# SW_SMALL.net
KiCad netlist of a schematic drawn in Altium Designer
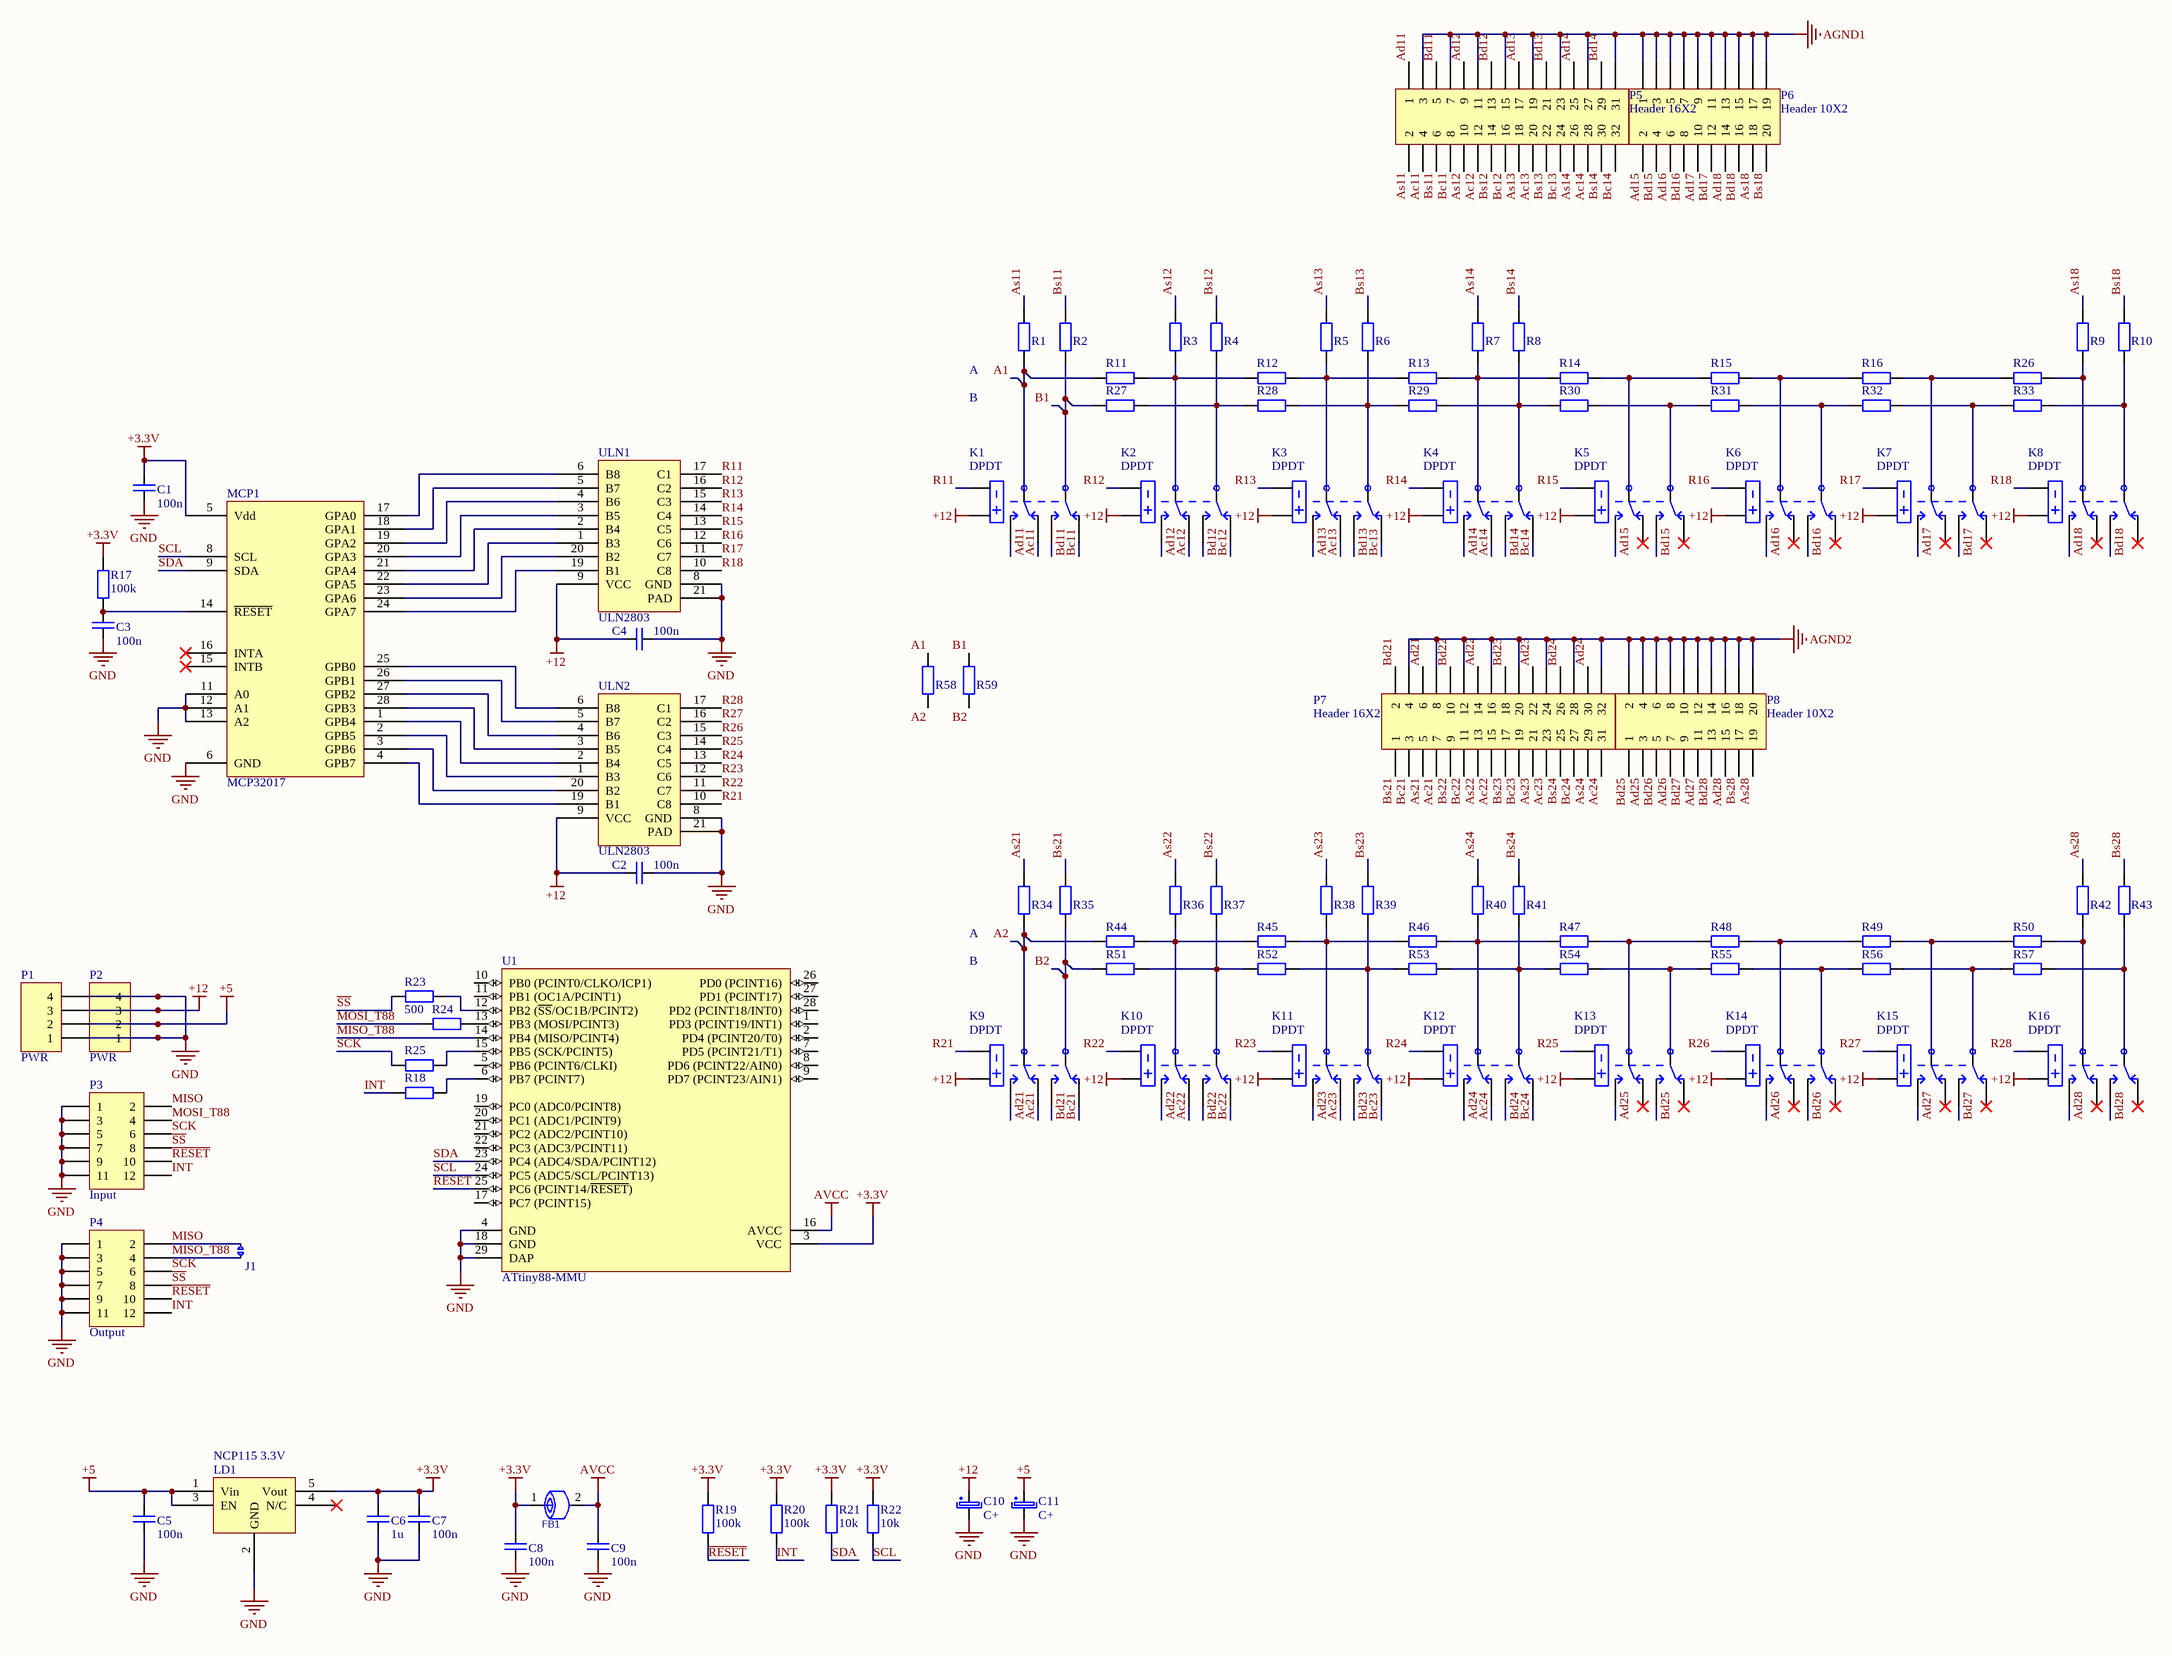
[diagram p0: SW SMALL.SchDoc]

(export (version "E")
  (design (tool "Eeschema 10.0.6"))
  (components
    (comp (ref "C1")
      (value "100n")
      (footprint "R1005_0402i_L")
      (description "Capacitor")
      (libsource (lib "General") (part "C"))
    )
    (comp (ref "C2")
      (value "100n")
      (footprint "R1005_0402i_L")
      (description "Capacitor")
      (libsource (lib "General") (part "C"))
    )
    (comp (ref "C3")
      (value "100n")
      (footprint "R1005_0402i_L")
      (description "Capacitor")
      (libsource (lib "General") (part "C"))
    )
    (comp (ref "C4")
      (value "100n")
      (footprint "R1005_0402i_L")
      (description "Capacitor")
      (libsource (lib "General") (part "C"))
    )
    (comp (ref "C5")
      (value "100n")
      (footprint "R1005_0402i_L")
      (description "Capacitor")
      (libsource (lib "General") (part "C"))
    )
    (comp (ref "C6")
      (value "1u")
      (footprint "C1608_0603I_L")
      (description "Capacitor")
      (libsource (lib "General") (part "C"))
    )
    (comp (ref "C7")
      (value "100n")
      (footprint "R1005_0402i_L")
      (description "Capacitor")
      (libsource (lib "General") (part "C"))
    )
    (comp (ref "C8")
      (value "100n")
      (footprint "R1005_0402i_L")
      (description "Capacitor")
      (libsource (lib "General") (part "C"))
    )
    (comp (ref "C9")
      (value "100n")
      (footprint "R1005_0402i_L")
      (description "Capacitor")
      (libsource (lib "General") (part "C"))
    )
    (comp (ref "C10")
      (value "C+")
      (footprint "C AlElko 5x11 R2")
      (description "Capacitor Polarized")
      (libsource (lib "General") (part "C+"))
    )
    (comp (ref "C11")
      (value "C+")
      (footprint "C AlElko 5x11 R2")
      (description "Capacitor Polarized")
      (libsource (lib "General") (part "C+"))
    )
    (comp (ref "FB1")
      (value "FERITTE BEAD")
      (footprint "R1608_0603I_L")
      (libsource (lib "General") (part "FERITTE BEAD"))
    )
    (comp (ref "J1")
      (value "Terminator")
      (footprint "solderJumper")
      (libsource (lib "Kon_Tipk") (part "JMP_mini"))
    )
    (comp (ref "K1")
      (value "DPDT")
      (footprint "AXICOM IM-G Relay")
      (description "TE CONNECTIVITY  IM-GR  RELAY, DPDT, NO")
      (libsource (lib "DistopikAltiumLibrary") (part "IM-GR Relay DPDT"))
    )
    (comp (ref "K2")
      (value "DPDT")
      (footprint "AXICOM IM-G Relay")
      (description "TE CONNECTIVITY  IM-GR  RELAY, DPDT, NO")
      (libsource (lib "DistopikAltiumLibrary") (part "IM-GR Relay DPDT"))
    )
    (comp (ref "K3")
      (value "DPDT")
      (footprint "AXICOM IM-G Relay")
      (description "TE CONNECTIVITY  IM-GR  RELAY, DPDT, NO")
      (libsource (lib "DistopikAltiumLibrary") (part "IM-GR Relay DPDT"))
    )
    (comp (ref "K4")
      (value "DPDT")
      (footprint "AXICOM IM-G Relay")
      (description "TE CONNECTIVITY  IM-GR  RELAY, DPDT, NO")
      (libsource (lib "DistopikAltiumLibrary") (part "IM-GR Relay DPDT"))
    )
    (comp (ref "K5")
      (value "DPDT")
      (footprint "AXICOM IM-G Relay")
      (description "TE CONNECTIVITY  IM-GR  RELAY, DPDT, NO")
      (libsource (lib "DistopikAltiumLibrary") (part "IM-GR Relay DPDT"))
    )
    (comp (ref "K6")
      (value "DPDT")
      (footprint "AXICOM IM-G Relay")
      (description "TE CONNECTIVITY  IM-GR  RELAY, DPDT, NO")
      (libsource (lib "DistopikAltiumLibrary") (part "IM-GR Relay DPDT"))
    )
    (comp (ref "K7")
      (value "DPDT")
      (footprint "AXICOM IM-G Relay")
      (description "TE CONNECTIVITY  IM-GR  RELAY, DPDT, NO")
      (libsource (lib "DistopikAltiumLibrary") (part "IM-GR Relay DPDT"))
    )
    (comp (ref "K8")
      (value "DPDT")
      (footprint "AXICOM IM-G Relay")
      (description "TE CONNECTIVITY  IM-GR  RELAY, DPDT, NO")
      (libsource (lib "DistopikAltiumLibrary") (part "IM-GR Relay DPDT"))
    )
    (comp (ref "K9")
      (value "DPDT")
      (footprint "AXICOM IM-G Relay")
      (description "TE CONNECTIVITY  IM-GR  RELAY, DPDT, NO")
      (libsource (lib "DistopikAltiumLibrary") (part "IM-GR Relay DPDT"))
    )
    (comp (ref "K10")
      (value "DPDT")
      (footprint "AXICOM IM-G Relay")
      (description "TE CONNECTIVITY  IM-GR  RELAY, DPDT, NO")
      (libsource (lib "DistopikAltiumLibrary") (part "IM-GR Relay DPDT"))
    )
    (comp (ref "K11")
      (value "DPDT")
      (footprint "AXICOM IM-G Relay")
      (description "TE CONNECTIVITY  IM-GR  RELAY, DPDT, NO")
      (libsource (lib "DistopikAltiumLibrary") (part "IM-GR Relay DPDT"))
    )
    (comp (ref "K12")
      (value "DPDT")
      (footprint "AXICOM IM-G Relay")
      (description "TE CONNECTIVITY  IM-GR  RELAY, DPDT, NO")
      (libsource (lib "DistopikAltiumLibrary") (part "IM-GR Relay DPDT"))
    )
    (comp (ref "K13")
      (value "DPDT")
      (footprint "AXICOM IM-G Relay")
      (description "TE CONNECTIVITY  IM-GR  RELAY, DPDT, NO")
      (libsource (lib "DistopikAltiumLibrary") (part "IM-GR Relay DPDT"))
    )
    (comp (ref "K14")
      (value "DPDT")
      (footprint "AXICOM IM-G Relay")
      (description "TE CONNECTIVITY  IM-GR  RELAY, DPDT, NO")
      (libsource (lib "DistopikAltiumLibrary") (part "IM-GR Relay DPDT"))
    )
    (comp (ref "K15")
      (value "DPDT")
      (footprint "AXICOM IM-G Relay")
      (description "TE CONNECTIVITY  IM-GR  RELAY, DPDT, NO")
      (libsource (lib "DistopikAltiumLibrary") (part "IM-GR Relay DPDT"))
    )
    (comp (ref "K16")
      (value "DPDT")
      (footprint "AXICOM IM-G Relay")
      (description "TE CONNECTIVITY  IM-GR  RELAY, DPDT, NO")
      (libsource (lib "DistopikAltiumLibrary") (part "IM-GR Relay DPDT"))
    )
    (comp (ref "LD1")
      (value "NCP115 3.3V")
      (footprint "TSOP95P280X110-6L")
      (libsource (lib "led_ring") (part "NCP115 3.3V"))
    )
    (comp (ref "MCP1")
      (value "MCP32017")
      (footprint "MCP23017 QFN")
      (libsource (lib "Schlib1") (part "MCP32017"))
    )
    (comp (ref "P1")
      (value "PWR")
      (footprint "HDR1X4")
      (description "Header, 4-Pin")
      (fields (field (name "PUBLISHER") "Altium Limited"))
      (libsource (lib "Miscellaneous Connectors") (part "Header 4"))
    )
    (comp (ref "P2")
      (value "PWR")
      (footprint "HDR1X4")
      (description "Header, 4-Pin")
      (fields (field (name "PUBLISHER") "Altium Limited"))
      (libsource (lib "Miscellaneous Connectors") (part "Header 4"))
    )
    (comp (ref "P3")
      (value "Input")
      (footprint "1.27mm SMD conn")
      (description "Header, 6-Pin, Dual row")
      (fields (field (name "PUBLISHER") "Altium Limited"))
      (libsource (lib "Miscellaneous Connectors") (part "Header 6X2"))
    )
    (comp (ref "P4")
      (value "Output")
      (footprint "1.27mm SMD conn")
      (description "Header, 6-Pin, Dual row")
      (fields (field (name "PUBLISHER") "Altium Limited"))
      (libsource (lib "Miscellaneous Connectors") (part "Header 6X2"))
    )
    (comp (ref "P5")
      (value "Header 16X2")
      (footprint "HDR2X16")
      (description "Header, 16-Pin, Dual row")
      (fields (field (name "PUBLISHER") "Altium Limited"))
      (libsource (lib "Miscellaneous Connectors") (part "Header 16X2"))
    )
    (comp (ref "P6")
      (value "Header 10X2")
      (footprint "HDR2X10")
      (description "Header, 10-Pin, Dual row")
      (fields (field (name "PUBLISHER") "Altium Limited"))
      (libsource (lib "") (part "Header 10X2_1"))
    )
    (comp (ref "P7")
      (value "Header 16X2")
      (footprint "HDR2X16")
      (description "Header, 16-Pin, Dual row")
      (fields (field (name "PUBLISHER") "Altium Limited"))
      (libsource (lib "") (part "Header 16X2_1"))
    )
    (comp (ref "P8")
      (value "Header 10X2")
      (footprint "HDR2X10")
      (description "Header, 10-Pin, Dual row")
      (fields (field (name "PUBLISHER") "Altium Limited"))
      (libsource (lib "Miscellaneous Connectors") (part "Header 10X2"))
    )
    (comp (ref "R1") (value "R") (footprint "R1608_0603I_L") (libsource (lib "General") (part "R")))
    (comp (ref "R2") (value "R") (footprint "R1608_0603I_L") (libsource (lib "General") (part "R")))
    (comp (ref "R3") (value "R") (footprint "R1608_0603I_L") (libsource (lib "General") (part "R")))
    (comp (ref "R4") (value "R") (footprint "R1608_0603I_L") (libsource (lib "General") (part "R")))
    (comp (ref "R5") (value "R") (footprint "R1608_0603I_L") (libsource (lib "General") (part "R")))
    (comp (ref "R6") (value "R") (footprint "R1608_0603I_L") (libsource (lib "General") (part "R")))
    (comp (ref "R7") (value "R") (footprint "R1608_0603I_L") (libsource (lib "General") (part "R")))
    (comp (ref "R8") (value "R") (footprint "R1608_0603I_L") (libsource (lib "General") (part "R")))
    (comp (ref "R9") (value "R") (footprint "R1608_0603I_L") (libsource (lib "General") (part "R")))
    (comp (ref "R10") (value "R") (footprint "R1608_0603I_L") (libsource (lib "General") (part "R")))
    (comp (ref "R11") (value "R") (footprint "R1608_0603I_L") (libsource (lib "General") (part "R")))
    (comp (ref "R12") (value "R") (footprint "R1608_0603I_L") (libsource (lib "General") (part "R")))
    (comp (ref "R13") (value "R") (footprint "R1608_0603I_L") (libsource (lib "General") (part "R")))
    (comp (ref "R14") (value "R") (footprint "R1608_0603I_L") (libsource (lib "General") (part "R")))
    (comp (ref "R15") (value "R") (footprint "R1608_0603I_L") (libsource (lib "General") (part "R")))
    (comp (ref "R16") (value "R") (footprint "R1608_0603I_L") (libsource (lib "General") (part "R")))
    (comp (ref "R17")
      (value "100k")
      (footprint "R1005_0402i_L")
      (description "R")
      (libsource (lib "General") (part "R"))
    )
    (comp (ref "R18")
      (value "500")
      (footprint "R1005_0402i_L")
      (description "R")
      (libsource (lib "General") (part "R"))
    )
    (comp (ref "R19")
      (value "100k")
      (footprint "R1005_0402i_L")
      (description "R")
      (libsource (lib "General") (part "R"))
    )
    (comp (ref "R20")
      (value "100k")
      (footprint "R1005_0402i_L")
      (description "R")
      (libsource (lib "General") (part "R"))
    )
    (comp (ref "R21")
      (value "10k")
      (footprint "R1005_0402i_L")
      (description "R")
      (libsource (lib "General") (part "R"))
    )
    (comp (ref "R22")
      (value "10k")
      (footprint "R1005_0402i_L")
      (description "R")
      (libsource (lib "General") (part "R"))
    )
    (comp (ref "R23")
      (value "500")
      (footprint "R1005_0402i_L")
      (description "R")
      (libsource (lib "General") (part "R"))
    )
    (comp (ref "R24")
      (value "500")
      (footprint "R1005_0402i_L")
      (description "R")
      (libsource (lib "General") (part "R"))
    )
    (comp (ref "R25")
      (value "500")
      (footprint "R1005_0402i_L")
      (description "R")
      (libsource (lib "General") (part "R"))
    )
    (comp (ref "R26") (value "R") (footprint "R1608_0603I_L") (libsource (lib "General") (part "R")))
    (comp (ref "R27") (value "R") (footprint "R1608_0603I_L") (libsource (lib "General") (part "R")))
    (comp (ref "R28") (value "R") (footprint "R1608_0603I_L") (libsource (lib "General") (part "R")))
    (comp (ref "R29") (value "R") (footprint "R1608_0603I_L") (libsource (lib "General") (part "R")))
    (comp (ref "R30") (value "R") (footprint "R1608_0603I_L") (libsource (lib "General") (part "R")))
    (comp (ref "R31") (value "R") (footprint "R1608_0603I_L") (libsource (lib "General") (part "R")))
    (comp (ref "R32") (value "R") (footprint "R1608_0603I_L") (libsource (lib "General") (part "R")))
    (comp (ref "R33") (value "R") (footprint "R1608_0603I_L") (libsource (lib "General") (part "R")))
    (comp (ref "R34") (value "R") (footprint "R1608_0603I_L") (libsource (lib "General") (part "R")))
    (comp (ref "R35") (value "R") (footprint "R1608_0603I_L") (libsource (lib "General") (part "R")))
    (comp (ref "R36") (value "R") (footprint "R1608_0603I_L") (libsource (lib "General") (part "R")))
    (comp (ref "R37") (value "R") (footprint "R1608_0603I_L") (libsource (lib "General") (part "R")))
    (comp (ref "R38") (value "R") (footprint "R1608_0603I_L") (libsource (lib "General") (part "R")))
    (comp (ref "R39") (value "R") (footprint "R1608_0603I_L") (libsource (lib "General") (part "R")))
    (comp (ref "R40") (value "R") (footprint "R1608_0603I_L") (libsource (lib "General") (part "R")))
    (comp (ref "R41") (value "R") (footprint "R1608_0603I_L") (libsource (lib "General") (part "R")))
    (comp (ref "R42") (value "R") (footprint "R1608_0603I_L") (libsource (lib "General") (part "R")))
    (comp (ref "R43") (value "R") (footprint "R1608_0603I_L") (libsource (lib "General") (part "R")))
    (comp (ref "R44") (value "R") (footprint "R1608_0603I_L") (libsource (lib "General") (part "R")))
    (comp (ref "R45") (value "R") (footprint "R1608_0603I_L") (libsource (lib "General") (part "R")))
    (comp (ref "R46") (value "R") (footprint "R1608_0603I_L") (libsource (lib "General") (part "R")))
    (comp (ref "R47") (value "R") (footprint "R1608_0603I_L") (libsource (lib "General") (part "R")))
    (comp (ref "R48") (value "R") (footprint "R1608_0603I_L") (libsource (lib "General") (part "R")))
    (comp (ref "R49") (value "R") (footprint "R1608_0603I_L") (libsource (lib "General") (part "R")))
    (comp (ref "R50") (value "R") (footprint "R1608_0603I_L") (libsource (lib "General") (part "R")))
    (comp (ref "R51") (value "R") (footprint "R1608_0603I_L") (libsource (lib "General") (part "R")))
    (comp (ref "R52") (value "R") (footprint "R1608_0603I_L") (libsource (lib "General") (part "R")))
    (comp (ref "R53") (value "R") (footprint "R1608_0603I_L") (libsource (lib "General") (part "R")))
    (comp (ref "R54") (value "R") (footprint "R1608_0603I_L") (libsource (lib "General") (part "R")))
    (comp (ref "R55") (value "R") (footprint "R1608_0603I_L") (libsource (lib "General") (part "R")))
    (comp (ref "R56") (value "R") (footprint "R1608_0603I_L") (libsource (lib "General") (part "R")))
    (comp (ref "R57") (value "R") (footprint "R1608_0603I_L") (libsource (lib "General") (part "R")))
    (comp (ref "R58") (value "R") (footprint "R1608_0603I_L") (libsource (lib "General") (part "R")))
    (comp (ref "R59") (value "R") (footprint "R1608_0603I_L") (libsource (lib "General") (part "R")))
    (comp (ref "U1")
      (value "ATtiny88-MMU")
      (footprint "28M1_N")
      (fields (field (name "PUBLISHER") "Altium Limited"))
      (libsource (lib "Encoder_w_LED_ring") (part "ATtiny88-MMU"))
    )
    (comp (ref "ULN1")
      (value "ULN2803")
      (footprint "QFN127P600-8N")
      (libsource (lib "Schlib1") (part "ULN2803"))
    )
    (comp (ref "ULN2")
      (value "ULN2803")
      (footprint "QFN127P600-8N")
      (libsource (lib "Schlib1") (part "ULN2803"))
    )
  )
  (nets
    (net (code "1") (name "+3.3V") (class "Default")
      (node (ref "C1") (pin "2") (pinfunction "2_2") (pintype "passive"))
      (node (ref "C6") (pin "1") (pinfunction "1_1") (pintype "passive"))
      (node (ref "C7") (pin "1") (pinfunction "1_1") (pintype "passive"))
      (node (ref "C8") (pin "1") (pinfunction "1_1") (pintype "passive"))
      (node (ref "FB1") (pin "1") (pintype "passive"))
      (node (ref "LD1") (pin "5") (pinfunction "Vout_5") (pintype "passive"))
      (node (ref "MCP1") (pin "5") (pinfunction "Vdd_5") (pintype "passive"))
      (node (ref "R17") (pin "1") (pintype "passive"))
      (node (ref "R19") (pin "1") (pintype "passive"))
      (node (ref "R20") (pin "1") (pintype "passive"))
      (node (ref "R21") (pin "1") (pintype "passive"))
      (node (ref "R22") (pin "1") (pintype "passive"))
      (node (ref "U1") (pin "3") (pinfunction "VCC_3") (pintype "power_in"))
    )
    (net (code "2") (name "+5") (class "Default")
      (node (ref "C11") (pin "1") (pinfunction "1_1") (pintype "passive"))
      (node (ref "C5") (pin "1") (pinfunction "1_1") (pintype "passive"))
      (node (ref "LD1") (pin "1") (pinfunction "Vin_1") (pintype "passive"))
      (node (ref "LD1") (pin "3") (pinfunction "EN_3") (pintype "passive"))
      (node (ref "P1") (pin "2") (pinfunction "2_2") (pintype "passive"))
      (node (ref "P2") (pin "2") (pinfunction "2_2") (pintype "passive"))
    )
    (net (code "3") (name "+12") (class "Default")
      (node (ref "C10") (pin "1") (pinfunction "1_1") (pintype "passive"))
      (node (ref "C2") (pin "1") (pinfunction "1_1") (pintype "passive"))
      (node (ref "C4") (pin "1") (pinfunction "1_1") (pintype "passive"))
      (node (ref "K1") (pin "1") (pinfunction "1_1") (pintype "passive"))
      (node (ref "K10") (pin "1") (pinfunction "1_1") (pintype "passive"))
      (node (ref "K11") (pin "1") (pinfunction "1_1") (pintype "passive"))
      (node (ref "K12") (pin "1") (pinfunction "1_1") (pintype "passive"))
      (node (ref "K13") (pin "1") (pinfunction "1_1") (pintype "passive"))
      (node (ref "K14") (pin "1") (pinfunction "1_1") (pintype "passive"))
      (node (ref "K15") (pin "1") (pinfunction "1_1") (pintype "passive"))
      (node (ref "K16") (pin "1") (pinfunction "1_1") (pintype "passive"))
      (node (ref "K2") (pin "1") (pinfunction "1_1") (pintype "passive"))
      (node (ref "K3") (pin "1") (pinfunction "1_1") (pintype "passive"))
      (node (ref "K4") (pin "1") (pinfunction "1_1") (pintype "passive"))
      (node (ref "K5") (pin "1") (pinfunction "1_1") (pintype "passive"))
      (node (ref "K6") (pin "1") (pinfunction "1_1") (pintype "passive"))
      (node (ref "K7") (pin "1") (pinfunction "1_1") (pintype "passive"))
      (node (ref "K8") (pin "1") (pinfunction "1_1") (pintype "passive"))
      (node (ref "K9") (pin "1") (pinfunction "1_1") (pintype "passive"))
      (node (ref "P1") (pin "3") (pinfunction "3_3") (pintype "passive"))
      (node (ref "P2") (pin "3") (pinfunction "3_3") (pintype "passive"))
      (node (ref "ULN1") (pin "9") (pinfunction "VCC_9") (pintype "passive"))
      (node (ref "ULN2") (pin "9") (pinfunction "VCC_9") (pintype "passive"))
    )
    (net (code "4") (name "/A1") (class "Default")
      (node (ref "K1") (pin "3") (pinfunction "3_3") (pintype "passive"))
      (node (ref "R1") (pin "1") (pintype "passive"))
      (node (ref "R11") (pin "1") (pintype "passive"))
      (node (ref "R58") (pin "2") (pintype "passive"))
    )
    (net (code "5") (name "/A2") (class "Default")
      (node (ref "K9") (pin "3") (pinfunction "3_3") (pintype "passive"))
      (node (ref "R34") (pin "1") (pintype "passive"))
      (node (ref "R44") (pin "1") (pintype "passive"))
      (node (ref "R58") (pin "1") (pintype "passive"))
    )
    (net (code "6") (name "/Ac11") (class "Default")
      (node (ref "K1") (pin "2") (pinfunction "2_2") (pintype "passive"))
      (node (ref "P5") (pin "4") (pinfunction "4_4") (pintype "passive"))
    )
    (net (code "7") (name "/Ac12") (class "Default")
      (node (ref "K2") (pin "2") (pinfunction "2_2") (pintype "passive"))
      (node (ref "P5") (pin "12") (pinfunction "12_12") (pintype "passive"))
    )
    (net (code "8") (name "/Ac13") (class "Default")
      (node (ref "K3") (pin "2") (pinfunction "2_2") (pintype "passive"))
      (node (ref "P5") (pin "20") (pinfunction "20_20") (pintype "passive"))
    )
    (net (code "9") (name "/Ac14") (class "Default")
      (node (ref "K4") (pin "2") (pinfunction "2_2") (pintype "passive"))
      (node (ref "P5") (pin "28") (pinfunction "28_28") (pintype "passive"))
    )
    (net (code "10") (name "/Ac21") (class "Default")
      (node (ref "K9") (pin "2") (pinfunction "2_2") (pintype "passive"))
      (node (ref "P7") (pin "7") (pinfunction "7_7") (pintype "passive"))
    )
    (net (code "11") (name "/Ac22") (class "Default")
      (node (ref "K10") (pin "2") (pinfunction "2_2") (pintype "passive"))
      (node (ref "P7") (pin "15") (pinfunction "15_15") (pintype "passive"))
    )
    (net (code "12") (name "/Ac23") (class "Default")
      (node (ref "K11") (pin "2") (pinfunction "2_2") (pintype "passive"))
      (node (ref "P7") (pin "23") (pinfunction "23_23") (pintype "passive"))
    )
    (net (code "13") (name "/Ac24") (class "Default")
      (node (ref "K12") (pin "2") (pinfunction "2_2") (pintype "passive"))
      (node (ref "P7") (pin "31") (pinfunction "31_31") (pintype "passive"))
    )
    (net (code "14") (name "/Ad11") (class "Default")
      (node (ref "K1") (pin "4") (pinfunction "4_4") (pintype "passive"))
      (node (ref "P5") (pin "1") (pinfunction "1_1") (pintype "passive"))
    )
    (net (code "15") (name "/Ad12") (class "Default")
      (node (ref "K2") (pin "4") (pinfunction "4_4") (pintype "passive"))
      (node (ref "P5") (pin "9") (pinfunction "9_9") (pintype "passive"))
    )
    (net (code "16") (name "/Ad13") (class "Default")
      (node (ref "K3") (pin "4") (pinfunction "4_4") (pintype "passive"))
      (node (ref "P5") (pin "17") (pinfunction "17_17") (pintype "passive"))
    )
    (net (code "17") (name "/Ad14") (class "Default")
      (node (ref "K4") (pin "4") (pinfunction "4_4") (pintype "passive"))
      (node (ref "P5") (pin "25") (pinfunction "25_25") (pintype "passive"))
    )
    (net (code "18") (name "/Ad15") (class "Default")
      (node (ref "K5") (pin "4") (pinfunction "4_4") (pintype "passive"))
      (node (ref "P6") (pin "2") (pinfunction "2_2") (pintype "passive"))
    )
    (net (code "19") (name "/Ad16") (class "Default")
      (node (ref "K6") (pin "4") (pinfunction "4_4") (pintype "passive"))
      (node (ref "P6") (pin "6") (pinfunction "6_6") (pintype "passive"))
    )
    (net (code "20") (name "/Ad17") (class "Default")
      (node (ref "K7") (pin "4") (pinfunction "4_4") (pintype "passive"))
      (node (ref "P6") (pin "10") (pinfunction "10_10") (pintype "passive"))
    )
    (net (code "21") (name "/Ad18") (class "Default")
      (node (ref "K8") (pin "4") (pinfunction "4_4") (pintype "passive"))
      (node (ref "P6") (pin "14") (pinfunction "14_14") (pintype "passive"))
    )
    (net (code "22") (name "/Ad21") (class "Default")
      (node (ref "K9") (pin "4") (pinfunction "4_4") (pintype "passive"))
      (node (ref "P7") (pin "6") (pinfunction "6_6") (pintype "passive"))
    )
    (net (code "23") (name "/Ad22") (class "Default")
      (node (ref "K10") (pin "4") (pinfunction "4_4") (pintype "passive"))
      (node (ref "P7") (pin "14") (pinfunction "14_14") (pintype "passive"))
    )
    (net (code "24") (name "/Ad23") (class "Default")
      (node (ref "K11") (pin "4") (pinfunction "4_4") (pintype "passive"))
      (node (ref "P7") (pin "22") (pinfunction "22_22") (pintype "passive"))
    )
    (net (code "25") (name "/Ad24") (class "Default")
      (node (ref "K12") (pin "4") (pinfunction "4_4") (pintype "passive"))
      (node (ref "P7") (pin "30") (pinfunction "30_30") (pintype "passive"))
    )
    (net (code "26") (name "/Ad25") (class "Default")
      (node (ref "K13") (pin "4") (pinfunction "4_4") (pintype "passive"))
      (node (ref "P8") (pin "3") (pinfunction "3_3") (pintype "passive"))
    )
    (net (code "27") (name "/Ad26") (class "Default")
      (node (ref "K14") (pin "4") (pinfunction "4_4") (pintype "passive"))
      (node (ref "P8") (pin "7") (pinfunction "7_7") (pintype "passive"))
    )
    (net (code "28") (name "/Ad27") (class "Default")
      (node (ref "K15") (pin "4") (pinfunction "4_4") (pintype "passive"))
      (node (ref "P8") (pin "11") (pinfunction "11_11") (pintype "passive"))
    )
    (net (code "29") (name "/Ad28") (class "Default")
      (node (ref "K16") (pin "4") (pinfunction "4_4") (pintype "passive"))
      (node (ref "P8") (pin "15") (pinfunction "15_15") (pintype "passive"))
    )
    (net (code "30") (name "/As11") (class "Default")
      (node (ref "P5") (pin "2") (pinfunction "2_2") (pintype "passive"))
      (node (ref "R1") (pin "2") (pintype "passive"))
    )
    (net (code "31") (name "/As12") (class "Default")
      (node (ref "P5") (pin "10") (pinfunction "10_10") (pintype "passive"))
      (node (ref "R3") (pin "2") (pintype "passive"))
    )
    (net (code "32") (name "/As13") (class "Default")
      (node (ref "P5") (pin "18") (pinfunction "18_18") (pintype "passive"))
      (node (ref "R5") (pin "2") (pintype "passive"))
    )
    (net (code "33") (name "/As14") (class "Default")
      (node (ref "P5") (pin "26") (pinfunction "26_26") (pintype "passive"))
      (node (ref "R7") (pin "2") (pintype "passive"))
    )
    (net (code "34") (name "/As18") (class "Default")
      (node (ref "P6") (pin "18") (pinfunction "18_18") (pintype "passive"))
      (node (ref "R9") (pin "2") (pintype "passive"))
    )
    (net (code "35") (name "/As21") (class "Default")
      (node (ref "P7") (pin "5") (pinfunction "5_5") (pintype "passive"))
      (node (ref "R34") (pin "2") (pintype "passive"))
    )
    (net (code "36") (name "/As22") (class "Default")
      (node (ref "P7") (pin "13") (pinfunction "13_13") (pintype "passive"))
      (node (ref "R36") (pin "2") (pintype "passive"))
    )
    (net (code "37") (name "/As23") (class "Default")
      (node (ref "P7") (pin "21") (pinfunction "21_21") (pintype "passive"))
      (node (ref "R38") (pin "2") (pintype "passive"))
    )
    (net (code "38") (name "/As24") (class "Default")
      (node (ref "P7") (pin "29") (pinfunction "29_29") (pintype "passive"))
      (node (ref "R40") (pin "2") (pintype "passive"))
    )
    (net (code "39") (name "/As28") (class "Default")
      (node (ref "P8") (pin "19") (pinfunction "19_19") (pintype "passive"))
      (node (ref "R42") (pin "2") (pintype "passive"))
    )
    (net (code "40") (name "/B1") (class "Default")
      (node (ref "K1") (pin "6") (pinfunction "6_6") (pintype "passive"))
      (node (ref "R2") (pin "1") (pintype "passive"))
      (node (ref "R27") (pin "1") (pintype "passive"))
      (node (ref "R59") (pin "2") (pintype "passive"))
    )
    (net (code "41") (name "/B2") (class "Default")
      (node (ref "K9") (pin "6") (pinfunction "6_6") (pintype "passive"))
      (node (ref "R35") (pin "1") (pintype "passive"))
      (node (ref "R51") (pin "1") (pintype "passive"))
      (node (ref "R59") (pin "1") (pintype "passive"))
    )
    (net (code "42") (name "/Bc11") (class "Default")
      (node (ref "K1") (pin "7") (pinfunction "7_7") (pintype "passive"))
      (node (ref "P5") (pin "8") (pinfunction "8_8") (pintype "passive"))
    )
    (net (code "43") (name "/Bc12") (class "Default")
      (node (ref "K2") (pin "7") (pinfunction "7_7") (pintype "passive"))
      (node (ref "P5") (pin "16") (pinfunction "16_16") (pintype "passive"))
    )
    (net (code "44") (name "/Bc13") (class "Default")
      (node (ref "K3") (pin "7") (pinfunction "7_7") (pintype "passive"))
      (node (ref "P5") (pin "24") (pinfunction "24_24") (pintype "passive"))
    )
    (net (code "45") (name "/Bc14") (class "Default")
      (node (ref "K4") (pin "7") (pinfunction "7_7") (pintype "passive"))
      (node (ref "P5") (pin "32") (pinfunction "32_32") (pintype "passive"))
    )
    (net (code "46") (name "/Bc21") (class "Default")
      (node (ref "K9") (pin "7") (pinfunction "7_7") (pintype "passive"))
      (node (ref "P7") (pin "3") (pinfunction "3_3") (pintype "passive"))
    )
    (net (code "47") (name "/Bc22") (class "Default")
      (node (ref "K10") (pin "7") (pinfunction "7_7") (pintype "passive"))
      (node (ref "P7") (pin "11") (pinfunction "11_11") (pintype "passive"))
    )
    (net (code "48") (name "/Bc23") (class "Default")
      (node (ref "K11") (pin "7") (pinfunction "7_7") (pintype "passive"))
      (node (ref "P7") (pin "19") (pinfunction "19_19") (pintype "passive"))
    )
    (net (code "49") (name "/Bc24") (class "Default")
      (node (ref "K12") (pin "7") (pinfunction "7_7") (pintype "passive"))
      (node (ref "P7") (pin "27") (pinfunction "27_27") (pintype "passive"))
    )
    (net (code "50") (name "/Bd11") (class "Default")
      (node (ref "K1") (pin "5") (pinfunction "5_5") (pintype "passive"))
      (node (ref "P5") (pin "5") (pinfunction "5_5") (pintype "passive"))
    )
    (net (code "51") (name "/Bd12") (class "Default")
      (node (ref "K2") (pin "5") (pinfunction "5_5") (pintype "passive"))
      (node (ref "P5") (pin "13") (pinfunction "13_13") (pintype "passive"))
    )
    (net (code "52") (name "/Bd13") (class "Default")
      (node (ref "K3") (pin "5") (pinfunction "5_5") (pintype "passive"))
      (node (ref "P5") (pin "21") (pinfunction "21_21") (pintype "passive"))
    )
    (net (code "53") (name "/Bd14") (class "Default")
      (node (ref "K4") (pin "5") (pinfunction "5_5") (pintype "passive"))
      (node (ref "P5") (pin "29") (pinfunction "29_29") (pintype "passive"))
    )
    (net (code "54") (name "/Bd15") (class "Default")
      (node (ref "K5") (pin "5") (pinfunction "5_5") (pintype "passive"))
      (node (ref "P6") (pin "4") (pinfunction "4_4") (pintype "passive"))
    )
    (net (code "55") (name "/Bd16") (class "Default")
      (node (ref "K6") (pin "5") (pinfunction "5_5") (pintype "passive"))
      (node (ref "P6") (pin "8") (pinfunction "8_8") (pintype "passive"))
    )
    (net (code "56") (name "/Bd17") (class "Default")
      (node (ref "K7") (pin "5") (pinfunction "5_5") (pintype "passive"))
      (node (ref "P6") (pin "12") (pinfunction "12_12") (pintype "passive"))
    )
    (net (code "57") (name "/Bd18") (class "Default")
      (node (ref "K8") (pin "5") (pinfunction "5_5") (pintype "passive"))
      (node (ref "P6") (pin "16") (pinfunction "16_16") (pintype "passive"))
    )
    (net (code "58") (name "/Bd21") (class "Default")
      (node (ref "K9") (pin "5") (pinfunction "5_5") (pintype "passive"))
      (node (ref "P7") (pin "2") (pinfunction "2_2") (pintype "passive"))
    )
    (net (code "59") (name "/Bd22") (class "Default")
      (node (ref "K10") (pin "5") (pinfunction "5_5") (pintype "passive"))
      (node (ref "P7") (pin "10") (pinfunction "10_10") (pintype "passive"))
    )
    (net (code "60") (name "/Bd23") (class "Default")
      (node (ref "K11") (pin "5") (pinfunction "5_5") (pintype "passive"))
      (node (ref "P7") (pin "18") (pinfunction "18_18") (pintype "passive"))
    )
    (net (code "61") (name "/Bd24") (class "Default")
      (node (ref "K12") (pin "5") (pinfunction "5_5") (pintype "passive"))
      (node (ref "P7") (pin "26") (pinfunction "26_26") (pintype "passive"))
    )
    (net (code "62") (name "/Bd25") (class "Default")
      (node (ref "K13") (pin "5") (pinfunction "5_5") (pintype "passive"))
      (node (ref "P8") (pin "1") (pinfunction "1_1") (pintype "passive"))
    )
    (net (code "63") (name "/Bd26") (class "Default")
      (node (ref "K14") (pin "5") (pinfunction "5_5") (pintype "passive"))
      (node (ref "P8") (pin "5") (pinfunction "5_5") (pintype "passive"))
    )
    (net (code "64") (name "/Bd27") (class "Default")
      (node (ref "K15") (pin "5") (pinfunction "5_5") (pintype "passive"))
      (node (ref "P8") (pin "9") (pinfunction "9_9") (pintype "passive"))
    )
    (net (code "65") (name "/Bd28") (class "Default")
      (node (ref "K16") (pin "5") (pinfunction "5_5") (pintype "passive"))
      (node (ref "P8") (pin "13") (pinfunction "13_13") (pintype "passive"))
    )
    (net (code "66") (name "/Bs11") (class "Default")
      (node (ref "P5") (pin "6") (pinfunction "6_6") (pintype "passive"))
      (node (ref "R2") (pin "2") (pintype "passive"))
    )
    (net (code "67") (name "/Bs12") (class "Default")
      (node (ref "P5") (pin "14") (pinfunction "14_14") (pintype "passive"))
      (node (ref "R4") (pin "2") (pintype "passive"))
    )
    (net (code "68") (name "/Bs13") (class "Default")
      (node (ref "P5") (pin "22") (pinfunction "22_22") (pintype "passive"))
      (node (ref "R6") (pin "2") (pintype "passive"))
    )
    (net (code "69") (name "/Bs14") (class "Default")
      (node (ref "P5") (pin "30") (pinfunction "30_30") (pintype "passive"))
      (node (ref "R8") (pin "2") (pintype "passive"))
    )
    (net (code "70") (name "/Bs18") (class "Default")
      (node (ref "P6") (pin "20") (pinfunction "20_20") (pintype "passive"))
      (node (ref "R10") (pin "2") (pintype "passive"))
    )
    (net (code "71") (name "/Bs21") (class "Default")
      (node (ref "P7") (pin "1") (pinfunction "1_1") (pintype "passive"))
      (node (ref "R35") (pin "2") (pintype "passive"))
    )
    (net (code "72") (name "/Bs22") (class "Default")
      (node (ref "P7") (pin "9") (pinfunction "9_9") (pintype "passive"))
      (node (ref "R37") (pin "2") (pintype "passive"))
    )
    (net (code "73") (name "/Bs23") (class "Default")
      (node (ref "P7") (pin "17") (pinfunction "17_17") (pintype "passive"))
      (node (ref "R39") (pin "2") (pintype "passive"))
    )
    (net (code "74") (name "/Bs24") (class "Default")
      (node (ref "P7") (pin "25") (pinfunction "25_25") (pintype "passive"))
      (node (ref "R41") (pin "2") (pintype "passive"))
    )
    (net (code "75") (name "/Bs28") (class "Default")
      (node (ref "P8") (pin "17") (pinfunction "17_17") (pintype "passive"))
      (node (ref "R43") (pin "2") (pintype "passive"))
    )
    (net (code "76") (name "/INT") (class "Default")
      (node (ref "P3") (pin "12") (pinfunction "12_12") (pintype "passive"))
      (node (ref "P4") (pin "12") (pinfunction "12_12") (pintype "passive"))
      (node (ref "R18") (pin "1") (pintype "passive"))
      (node (ref "R20") (pin "2") (pintype "passive"))
    )
    (net (code "77") (name "/MISO") (class "Default")
      (node (ref "J1") (pin "2") (pinfunction "2_2") (pintype "passive"))
      (node (ref "P3") (pin "2") (pinfunction "2_2") (pintype "passive"))
      (node (ref "P4") (pin "2") (pinfunction "2_2") (pintype "passive"))
    )
    (net (code "78") (name "/MISO_T88") (class "Default")
      (node (ref "J1") (pin "1") (pinfunction "1_1") (pintype "passive"))
      (node (ref "P4") (pin "4") (pinfunction "4_4") (pintype "passive"))
      (node (ref "U1") (pin "14") (pinfunction "PB4_(MISO/PCINT4)_14") (pintype "bidirectional"))
    )
    (net (code "79") (name "/MOSI_T88") (class "Default")
      (node (ref "P3") (pin "4") (pinfunction "4_4") (pintype "passive"))
      (node (ref "R24") (pin "1") (pintype "passive"))
    )
    (net (code "80") (name "/R11") (class "Default")
      (node (ref "K1") (pin "8") (pinfunction "8_8") (pintype "passive"))
      (node (ref "ULN1") (pin "17") (pinfunction "C1_17") (pintype "passive"))
    )
    (net (code "81") (name "/R12") (class "Default")
      (node (ref "K2") (pin "8") (pinfunction "8_8") (pintype "passive"))
      (node (ref "ULN1") (pin "16") (pinfunction "C2_16") (pintype "passive"))
    )
    (net (code "82") (name "/R13") (class "Default")
      (node (ref "K3") (pin "8") (pinfunction "8_8") (pintype "passive"))
      (node (ref "ULN1") (pin "15") (pinfunction "C3_15") (pintype "passive"))
    )
    (net (code "83") (name "/R14") (class "Default")
      (node (ref "K4") (pin "8") (pinfunction "8_8") (pintype "passive"))
      (node (ref "ULN1") (pin "14") (pinfunction "C4_14") (pintype "passive"))
    )
    (net (code "84") (name "/R15") (class "Default")
      (node (ref "K5") (pin "8") (pinfunction "8_8") (pintype "passive"))
      (node (ref "ULN1") (pin "13") (pinfunction "C5_13") (pintype "passive"))
    )
    (net (code "85") (name "/R16") (class "Default")
      (node (ref "K6") (pin "8") (pinfunction "8_8") (pintype "passive"))
      (node (ref "ULN1") (pin "12") (pinfunction "C6_12") (pintype "passive"))
    )
    (net (code "86") (name "/R17") (class "Default")
      (node (ref "K7") (pin "8") (pinfunction "8_8") (pintype "passive"))
      (node (ref "ULN1") (pin "11") (pinfunction "C7_11") (pintype "passive"))
    )
    (net (code "87") (name "/R18") (class "Default")
      (node (ref "K8") (pin "8") (pinfunction "8_8") (pintype "passive"))
      (node (ref "ULN1") (pin "10") (pinfunction "C8_10") (pintype "passive"))
    )
    (net (code "88") (name "/R21") (class "Default")
      (node (ref "K9") (pin "8") (pinfunction "8_8") (pintype "passive"))
      (node (ref "ULN2") (pin "10") (pinfunction "C8_10") (pintype "passive"))
    )
    (net (code "89") (name "/R22") (class "Default")
      (node (ref "K10") (pin "8") (pinfunction "8_8") (pintype "passive"))
      (node (ref "ULN2") (pin "11") (pinfunction "C7_11") (pintype "passive"))
    )
    (net (code "90") (name "/R23") (class "Default")
      (node (ref "K11") (pin "8") (pinfunction "8_8") (pintype "passive"))
      (node (ref "ULN2") (pin "12") (pinfunction "C6_12") (pintype "passive"))
    )
    (net (code "91") (name "/R24") (class "Default")
      (node (ref "K12") (pin "8") (pinfunction "8_8") (pintype "passive"))
      (node (ref "ULN2") (pin "13") (pinfunction "C5_13") (pintype "passive"))
    )
    (net (code "92") (name "/R25") (class "Default")
      (node (ref "K13") (pin "8") (pinfunction "8_8") (pintype "passive"))
      (node (ref "ULN2") (pin "14") (pinfunction "C4_14") (pintype "passive"))
    )
    (net (code "93") (name "/R26") (class "Default")
      (node (ref "K14") (pin "8") (pinfunction "8_8") (pintype "passive"))
      (node (ref "ULN2") (pin "15") (pinfunction "C3_15") (pintype "passive"))
    )
    (net (code "94") (name "/R27") (class "Default")
      (node (ref "K15") (pin "8") (pinfunction "8_8") (pintype "passive"))
      (node (ref "ULN2") (pin "16") (pinfunction "C2_16") (pintype "passive"))
    )
    (net (code "95") (name "/R28") (class "Default")
      (node (ref "K16") (pin "8") (pinfunction "8_8") (pintype "passive"))
      (node (ref "ULN2") (pin "17") (pinfunction "C1_17") (pintype "passive"))
    )
    (net (code "96") (name "/SCK") (class "Default")
      (node (ref "P3") (pin "6") (pinfunction "6_6") (pintype "passive"))
      (node (ref "P4") (pin "6") (pinfunction "6_6") (pintype "passive"))
      (node (ref "R25") (pin "1") (pintype "passive"))
    )
    (net (code "97") (name "/SCL") (class "Default")
      (node (ref "MCP1") (pin "8") (pinfunction "SCL_8") (pintype "passive"))
      (node (ref "R22") (pin "2") (pintype "passive"))
      (node (ref "U1") (pin "24") (pinfunction "PC5_(ADC5/SCL/PCINT13)_24") (pintype "bidirectional"))
    )
    (net (code "98") (name "/SDA") (class "Default")
      (node (ref "MCP1") (pin "9") (pinfunction "SDA_9") (pintype "passive"))
      (node (ref "R21") (pin "2") (pintype "passive"))
      (node (ref "U1") (pin "23") (pinfunction "PC4_(ADC4/SDA/PCINT12)_23") (pintype "bidirectional"))
    )
    (net (code "99") (name "/~{RESET}") (class "Default")
      (node (ref "P3") (pin "10") (pinfunction "10_10") (pintype "passive"))
      (node (ref "P4") (pin "10") (pinfunction "10_10") (pintype "passive"))
      (node (ref "R19") (pin "2") (pintype "passive"))
      (node (ref "U1") (pin "25") (pinfunction "PC6_(PCINT14/~{RESET})_25") (pintype "bidirectional"))
    )
    (net (code "100") (name "/~{SS}") (class "Default")
      (node (ref "P3") (pin "8") (pinfunction "8_8") (pintype "passive"))
      (node (ref "P4") (pin "8") (pinfunction "8_8") (pintype "passive"))
      (node (ref "R23") (pin "1") (pintype "passive"))
    )
    (net (code "101") (name "AGND1") (class "Default")
      (node (ref "P5") (pin "11") (pinfunction "11_11") (pintype "passive"))
      (node (ref "P5") (pin "15") (pinfunction "15_15") (pintype "passive"))
      (node (ref "P5") (pin "19") (pinfunction "19_19") (pintype "passive"))
      (node (ref "P5") (pin "23") (pinfunction "23_23") (pintype "passive"))
      (node (ref "P5") (pin "27") (pinfunction "27_27") (pintype "passive"))
      (node (ref "P5") (pin "3") (pinfunction "3_3") (pintype "passive"))
      (node (ref "P5") (pin "31") (pinfunction "31_31") (pintype "passive"))
      (node (ref "P5") (pin "7") (pinfunction "7_7") (pintype "passive"))
      (node (ref "P6") (pin "1") (pinfunction "1_1") (pintype "passive"))
      (node (ref "P6") (pin "11") (pinfunction "11_11") (pintype "passive"))
      (node (ref "P6") (pin "13") (pinfunction "13_13") (pintype "passive"))
      (node (ref "P6") (pin "15") (pinfunction "15_15") (pintype "passive"))
      (node (ref "P6") (pin "17") (pinfunction "17_17") (pintype "passive"))
      (node (ref "P6") (pin "19") (pinfunction "19_19") (pintype "passive"))
      (node (ref "P6") (pin "3") (pinfunction "3_3") (pintype "passive"))
      (node (ref "P6") (pin "5") (pinfunction "5_5") (pintype "passive"))
      (node (ref "P6") (pin "7") (pinfunction "7_7") (pintype "passive"))
      (node (ref "P6") (pin "9") (pinfunction "9_9") (pintype "passive"))
    )
    (net (code "102") (name "AGND2") (class "Default")
      (node (ref "P7") (pin "12") (pinfunction "12_12") (pintype "passive"))
      (node (ref "P7") (pin "16") (pinfunction "16_16") (pintype "passive"))
      (node (ref "P7") (pin "20") (pinfunction "20_20") (pintype "passive"))
      (node (ref "P7") (pin "24") (pinfunction "24_24") (pintype "passive"))
      (node (ref "P7") (pin "28") (pinfunction "28_28") (pintype "passive"))
      (node (ref "P7") (pin "32") (pinfunction "32_32") (pintype "passive"))
      (node (ref "P7") (pin "4") (pinfunction "4_4") (pintype "passive"))
      (node (ref "P7") (pin "8") (pinfunction "8_8") (pintype "passive"))
      (node (ref "P8") (pin "10") (pinfunction "10_10") (pintype "passive"))
      (node (ref "P8") (pin "12") (pinfunction "12_12") (pintype "passive"))
      (node (ref "P8") (pin "14") (pinfunction "14_14") (pintype "passive"))
      (node (ref "P8") (pin "16") (pinfunction "16_16") (pintype "passive"))
      (node (ref "P8") (pin "18") (pinfunction "18_18") (pintype "passive"))
      (node (ref "P8") (pin "2") (pinfunction "2_2") (pintype "passive"))
      (node (ref "P8") (pin "20") (pinfunction "20_20") (pintype "passive"))
      (node (ref "P8") (pin "4") (pinfunction "4_4") (pintype "passive"))
      (node (ref "P8") (pin "6") (pinfunction "6_6") (pintype "passive"))
      (node (ref "P8") (pin "8") (pinfunction "8_8") (pintype "passive"))
    )
    (net (code "103") (name "AVCC") (class "Default")
      (node (ref "C9") (pin "1") (pinfunction "1_1") (pintype "passive"))
      (node (ref "FB1") (pin "2") (pintype "passive"))
      (node (ref "U1") (pin "16") (pinfunction "AVCC_16") (pintype "power_in"))
    )
    (net (code "104") (name "GND") (class "Default")
      (node (ref "C1") (pin "1") (pinfunction "1_1") (pintype "passive"))
      (node (ref "C10") (pin "2") (pinfunction "2_2") (pintype "passive"))
      (node (ref "C11") (pin "2") (pinfunction "2_2") (pintype "passive"))
      (node (ref "C2") (pin "2") (pinfunction "2_2") (pintype "passive"))
      (node (ref "C3") (pin "1") (pinfunction "1_1") (pintype "passive"))
      (node (ref "C4") (pin "2") (pinfunction "2_2") (pintype "passive"))
      (node (ref "C5") (pin "2") (pinfunction "2_2") (pintype "passive"))
      (node (ref "C6") (pin "2") (pinfunction "2_2") (pintype "passive"))
      (node (ref "C7") (pin "2") (pinfunction "2_2") (pintype "passive"))
      (node (ref "C8") (pin "2") (pinfunction "2_2") (pintype "passive"))
      (node (ref "C9") (pin "2") (pinfunction "2_2") (pintype "passive"))
      (node (ref "LD1") (pin "2") (pinfunction "GND_2") (pintype "passive"))
      (node (ref "MCP1") (pin "11") (pinfunction "A0_11") (pintype "passive"))
      (node (ref "MCP1") (pin "12") (pinfunction "A1_12") (pintype "passive"))
      (node (ref "MCP1") (pin "13") (pinfunction "A2_13") (pintype "passive"))
      (node (ref "MCP1") (pin "6") (pinfunction "GND_6") (pintype "passive"))
      (node (ref "P1") (pin "1") (pinfunction "1_1") (pintype "passive"))
      (node (ref "P1") (pin "4") (pinfunction "4_4") (pintype "passive"))
      (node (ref "P2") (pin "1") (pinfunction "1_1") (pintype "passive"))
      (node (ref "P2") (pin "4") (pinfunction "4_4") (pintype "passive"))
      (node (ref "P3") (pin "1") (pinfunction "1_1") (pintype "passive"))
      (node (ref "P3") (pin "11") (pinfunction "11_11") (pintype "passive"))
      (node (ref "P3") (pin "3") (pinfunction "3_3") (pintype "passive"))
      (node (ref "P3") (pin "5") (pinfunction "5_5") (pintype "passive"))
      (node (ref "P3") (pin "7") (pinfunction "7_7") (pintype "passive"))
      (node (ref "P3") (pin "9") (pinfunction "9_9") (pintype "passive"))
      (node (ref "P4") (pin "1") (pinfunction "1_1") (pintype "passive"))
      (node (ref "P4") (pin "11") (pinfunction "11_11") (pintype "passive"))
      (node (ref "P4") (pin "3") (pinfunction "3_3") (pintype "passive"))
      (node (ref "P4") (pin "5") (pinfunction "5_5") (pintype "passive"))
      (node (ref "P4") (pin "7") (pinfunction "7_7") (pintype "passive"))
      (node (ref "P4") (pin "9") (pinfunction "9_9") (pintype "passive"))
      (node (ref "U1") (pin "18") (pinfunction "GND_18") (pintype "power_in"))
      (node (ref "U1") (pin "29") (pinfunction "DAP_29") (pintype "passive"))
      (node (ref "U1") (pin "4") (pinfunction "GND_4") (pintype "power_in"))
      (node (ref "ULN1") (pin "21") (pinfunction "PAD_21") (pintype "passive"))
      (node (ref "ULN1") (pin "8") (pinfunction "GND_8") (pintype "passive"))
      (node (ref "ULN2") (pin "21") (pinfunction "PAD_21") (pintype "passive"))
      (node (ref "ULN2") (pin "8") (pinfunction "GND_8") (pintype "passive"))
    )
    (net (code "105") (name "Net-(K2-Pad3)") (class "Default")
      (node (ref "K2") (pin "3") (pinfunction "3_3") (pintype "passive"))
      (node (ref "R11") (pin "2") (pintype "passive"))
      (node (ref "R12") (pin "1") (pintype "passive"))
      (node (ref "R3") (pin "1") (pintype "passive"))
    )
    (net (code "106") (name "Net-(K2-Pad6)") (class "Default")
      (node (ref "K2") (pin "6") (pinfunction "6_6") (pintype "passive"))
      (node (ref "R27") (pin "2") (pintype "passive"))
      (node (ref "R28") (pin "1") (pintype "passive"))
      (node (ref "R4") (pin "1") (pintype "passive"))
    )
    (net (code "107") (name "Net-(K3-Pad3)") (class "Default")
      (node (ref "K3") (pin "3") (pinfunction "3_3") (pintype "passive"))
      (node (ref "R12") (pin "2") (pintype "passive"))
      (node (ref "R13") (pin "1") (pintype "passive"))
      (node (ref "R5") (pin "1") (pintype "passive"))
    )
    (net (code "108") (name "Net-(K3-Pad6)") (class "Default")
      (node (ref "K3") (pin "6") (pinfunction "6_6") (pintype "passive"))
      (node (ref "R28") (pin "2") (pintype "passive"))
      (node (ref "R29") (pin "1") (pintype "passive"))
      (node (ref "R6") (pin "1") (pintype "passive"))
    )
    (net (code "109") (name "Net-(K4-Pad3)") (class "Default")
      (node (ref "K4") (pin "3") (pinfunction "3_3") (pintype "passive"))
      (node (ref "R13") (pin "2") (pintype "passive"))
      (node (ref "R14") (pin "1") (pintype "passive"))
      (node (ref "R7") (pin "1") (pintype "passive"))
    )
    (net (code "110") (name "Net-(K4-Pad6)") (class "Default")
      (node (ref "K4") (pin "6") (pinfunction "6_6") (pintype "passive"))
      (node (ref "R29") (pin "2") (pintype "passive"))
      (node (ref "R30") (pin "1") (pintype "passive"))
      (node (ref "R8") (pin "1") (pintype "passive"))
    )
    (net (code "111") (name "Net-(K5-Pad3)") (class "Default")
      (node (ref "K5") (pin "3") (pinfunction "3_3") (pintype "passive"))
      (node (ref "R14") (pin "2") (pintype "passive"))
      (node (ref "R15") (pin "1") (pintype "passive"))
    )
    (net (code "112") (name "Net-(K5-Pad6)") (class "Default")
      (node (ref "K5") (pin "6") (pinfunction "6_6") (pintype "passive"))
      (node (ref "R30") (pin "2") (pintype "passive"))
      (node (ref "R31") (pin "1") (pintype "passive"))
    )
    (net (code "113") (name "Net-(K6-Pad3)") (class "Default")
      (node (ref "K6") (pin "3") (pinfunction "3_3") (pintype "passive"))
      (node (ref "R15") (pin "2") (pintype "passive"))
      (node (ref "R16") (pin "1") (pintype "passive"))
    )
    (net (code "114") (name "Net-(K6-Pad6)") (class "Default")
      (node (ref "K6") (pin "6") (pinfunction "6_6") (pintype "passive"))
      (node (ref "R31") (pin "2") (pintype "passive"))
      (node (ref "R32") (pin "1") (pintype "passive"))
    )
    (net (code "115") (name "Net-(K7-Pad3)") (class "Default")
      (node (ref "K7") (pin "3") (pinfunction "3_3") (pintype "passive"))
      (node (ref "R16") (pin "2") (pintype "passive"))
      (node (ref "R26") (pin "1") (pintype "passive"))
    )
    (net (code "116") (name "Net-(K7-Pad6)") (class "Default")
      (node (ref "K7") (pin "6") (pinfunction "6_6") (pintype "passive"))
      (node (ref "R32") (pin "2") (pintype "passive"))
      (node (ref "R33") (pin "1") (pintype "passive"))
    )
    (net (code "117") (name "Net-(K8-Pad3)") (class "Default")
      (node (ref "K8") (pin "3") (pinfunction "3_3") (pintype "passive"))
      (node (ref "R26") (pin "2") (pintype "passive"))
      (node (ref "R9") (pin "1") (pintype "passive"))
    )
    (net (code "118") (name "Net-(K8-Pad6)") (class "Default")
      (node (ref "K8") (pin "6") (pinfunction "6_6") (pintype "passive"))
      (node (ref "R10") (pin "1") (pintype "passive"))
      (node (ref "R33") (pin "2") (pintype "passive"))
    )
    (net (code "119") (name "Net-(K10-Pad3)") (class "Default")
      (node (ref "K10") (pin "3") (pinfunction "3_3") (pintype "passive"))
      (node (ref "R36") (pin "1") (pintype "passive"))
      (node (ref "R44") (pin "2") (pintype "passive"))
      (node (ref "R45") (pin "1") (pintype "passive"))
    )
    (net (code "120") (name "Net-(K10-Pad6)") (class "Default")
      (node (ref "K10") (pin "6") (pinfunction "6_6") (pintype "passive"))
      (node (ref "R37") (pin "1") (pintype "passive"))
      (node (ref "R51") (pin "2") (pintype "passive"))
      (node (ref "R52") (pin "1") (pintype "passive"))
    )
    (net (code "121") (name "Net-(K11-Pad3)") (class "Default")
      (node (ref "K11") (pin "3") (pinfunction "3_3") (pintype "passive"))
      (node (ref "R38") (pin "1") (pintype "passive"))
      (node (ref "R45") (pin "2") (pintype "passive"))
      (node (ref "R46") (pin "1") (pintype "passive"))
    )
    (net (code "122") (name "Net-(K11-Pad6)") (class "Default")
      (node (ref "K11") (pin "6") (pinfunction "6_6") (pintype "passive"))
      (node (ref "R39") (pin "1") (pintype "passive"))
      (node (ref "R52") (pin "2") (pintype "passive"))
      (node (ref "R53") (pin "1") (pintype "passive"))
    )
    (net (code "123") (name "Net-(K12-Pad3)") (class "Default")
      (node (ref "K12") (pin "3") (pinfunction "3_3") (pintype "passive"))
      (node (ref "R40") (pin "1") (pintype "passive"))
      (node (ref "R46") (pin "2") (pintype "passive"))
      (node (ref "R47") (pin "1") (pintype "passive"))
    )
    (net (code "124") (name "Net-(K12-Pad6)") (class "Default")
      (node (ref "K12") (pin "6") (pinfunction "6_6") (pintype "passive"))
      (node (ref "R41") (pin "1") (pintype "passive"))
      (node (ref "R53") (pin "2") (pintype "passive"))
      (node (ref "R54") (pin "1") (pintype "passive"))
    )
    (net (code "125") (name "Net-(K13-Pad3)") (class "Default")
      (node (ref "K13") (pin "3") (pinfunction "3_3") (pintype "passive"))
      (node (ref "R47") (pin "2") (pintype "passive"))
      (node (ref "R48") (pin "1") (pintype "passive"))
    )
    (net (code "126") (name "Net-(K13-Pad6)") (class "Default")
      (node (ref "K13") (pin "6") (pinfunction "6_6") (pintype "passive"))
      (node (ref "R54") (pin "2") (pintype "passive"))
      (node (ref "R55") (pin "1") (pintype "passive"))
    )
    (net (code "127") (name "Net-(K14-Pad3)") (class "Default")
      (node (ref "K14") (pin "3") (pinfunction "3_3") (pintype "passive"))
      (node (ref "R48") (pin "2") (pintype "passive"))
      (node (ref "R49") (pin "1") (pintype "passive"))
    )
    (net (code "128") (name "Net-(K14-Pad6)") (class "Default")
      (node (ref "K14") (pin "6") (pinfunction "6_6") (pintype "passive"))
      (node (ref "R55") (pin "2") (pintype "passive"))
      (node (ref "R56") (pin "1") (pintype "passive"))
    )
    (net (code "129") (name "Net-(K15-Pad3)") (class "Default")
      (node (ref "K15") (pin "3") (pinfunction "3_3") (pintype "passive"))
      (node (ref "R49") (pin "2") (pintype "passive"))
      (node (ref "R50") (pin "1") (pintype "passive"))
    )
    (net (code "130") (name "Net-(K15-Pad6)") (class "Default")
      (node (ref "K15") (pin "6") (pinfunction "6_6") (pintype "passive"))
      (node (ref "R56") (pin "2") (pintype "passive"))
      (node (ref "R57") (pin "1") (pintype "passive"))
    )
    (net (code "131") (name "Net-(K16-Pad3)") (class "Default")
      (node (ref "K16") (pin "3") (pinfunction "3_3") (pintype "passive"))
      (node (ref "R42") (pin "1") (pintype "passive"))
      (node (ref "R50") (pin "2") (pintype "passive"))
    )
    (net (code "132") (name "Net-(K16-Pad6)") (class "Default")
      (node (ref "K16") (pin "6") (pinfunction "6_6") (pintype "passive"))
      (node (ref "R43") (pin "1") (pintype "passive"))
      (node (ref "R57") (pin "2") (pintype "passive"))
    )
    (net (code "133") (name "Net-(MCP1-GPA0)") (class "Default")
      (node (ref "MCP1") (pin "17") (pinfunction "GPA0_17") (pintype "passive"))
      (node (ref "ULN1") (pin "6") (pinfunction "B8_6") (pintype "passive"))
    )
    (net (code "134") (name "Net-(MCP1-GPA1)") (class "Default")
      (node (ref "MCP1") (pin "18") (pinfunction "GPA1_18") (pintype "passive"))
      (node (ref "ULN1") (pin "5") (pinfunction "B7_5") (pintype "passive"))
    )
    (net (code "135") (name "Net-(MCP1-GPA2)") (class "Default")
      (node (ref "MCP1") (pin "19") (pinfunction "GPA2_19") (pintype "passive"))
      (node (ref "ULN1") (pin "4") (pinfunction "B6_4") (pintype "passive"))
    )
    (net (code "136") (name "Net-(MCP1-GPA3)") (class "Default")
      (node (ref "MCP1") (pin "20") (pinfunction "GPA3_20") (pintype "passive"))
      (node (ref "ULN1") (pin "3") (pinfunction "B5_3") (pintype "passive"))
    )
    (net (code "137") (name "Net-(MCP1-GPA4)") (class "Default")
      (node (ref "MCP1") (pin "21") (pinfunction "GPA4_21") (pintype "passive"))
      (node (ref "ULN1") (pin "2") (pinfunction "B4_2") (pintype "passive"))
    )
    (net (code "138") (name "Net-(MCP1-GPA5)") (class "Default")
      (node (ref "MCP1") (pin "22") (pinfunction "GPA5_22") (pintype "passive"))
      (node (ref "ULN1") (pin "1") (pinfunction "B3_1") (pintype "passive"))
    )
    (net (code "139") (name "Net-(MCP1-GPA6)") (class "Default")
      (node (ref "MCP1") (pin "23") (pinfunction "GPA6_23") (pintype "passive"))
      (node (ref "ULN1") (pin "20") (pinfunction "B2_20") (pintype "passive"))
    )
    (net (code "140") (name "Net-(MCP1-GPA7)") (class "Default")
      (node (ref "MCP1") (pin "24") (pinfunction "GPA7_24") (pintype "passive"))
      (node (ref "ULN1") (pin "19") (pinfunction "B1_19") (pintype "passive"))
    )
    (net (code "141") (name "Net-(MCP1-GPB0)") (class "Default")
      (node (ref "MCP1") (pin "25") (pinfunction "GPB0_25") (pintype "passive"))
      (node (ref "ULN2") (pin "6") (pinfunction "B8_6") (pintype "passive"))
    )
    (net (code "142") (name "Net-(MCP1-GPB1)") (class "Default")
      (node (ref "MCP1") (pin "26") (pinfunction "GPB1_26") (pintype "passive"))
      (node (ref "ULN2") (pin "5") (pinfunction "B7_5") (pintype "passive"))
    )
    (net (code "143") (name "Net-(MCP1-GPB2)") (class "Default")
      (node (ref "MCP1") (pin "27") (pinfunction "GPB2_27") (pintype "passive"))
      (node (ref "ULN2") (pin "4") (pinfunction "B6_4") (pintype "passive"))
    )
    (net (code "144") (name "Net-(MCP1-GPB3)") (class "Default")
      (node (ref "MCP1") (pin "28") (pinfunction "GPB3_28") (pintype "passive"))
      (node (ref "ULN2") (pin "3") (pinfunction "B5_3") (pintype "passive"))
    )
    (net (code "145") (name "Net-(MCP1-GPB4)") (class "Default")
      (node (ref "MCP1") (pin "1") (pinfunction "GPB4_1") (pintype "passive"))
      (node (ref "ULN2") (pin "2") (pinfunction "B4_2") (pintype "passive"))
    )
    (net (code "146") (name "Net-(MCP1-GPB5)") (class "Default")
      (node (ref "MCP1") (pin "2") (pinfunction "GPB5_2") (pintype "passive"))
      (node (ref "ULN2") (pin "1") (pinfunction "B3_1") (pintype "passive"))
    )
    (net (code "147") (name "Net-(MCP1-GPB6)") (class "Default")
      (node (ref "MCP1") (pin "3") (pinfunction "GPB6_3") (pintype "passive"))
      (node (ref "ULN2") (pin "20") (pinfunction "B2_20") (pintype "passive"))
    )
    (net (code "148") (name "Net-(MCP1-GPB7)") (class "Default")
      (node (ref "MCP1") (pin "4") (pinfunction "GPB7_4") (pintype "passive"))
      (node (ref "ULN2") (pin "19") (pinfunction "B1_19") (pintype "passive"))
    )
    (net (code "149") (name "Net-(MCP1-~{RESET})") (class "Default")
      (node (ref "C3") (pin "2") (pinfunction "2_2") (pintype "passive"))
      (node (ref "MCP1") (pin "14") (pinfunction "~{RESET}_14") (pintype "passive"))
      (node (ref "R17") (pin "2") (pintype "passive"))
    )
    (net (code "150") (name "Net-(U1-PB2_(~{SS}{slash}OC1B{slash}PCINT2))") (class "Default")
      (node (ref "R23") (pin "2") (pintype "passive"))
      (node (ref "U1") (pin "12") (pinfunction "PB2_(~{SS}/OC1B/PCINT2)_12") (pintype "bidirectional"))
    )
    (net (code "151") (name "Net-(U1-PB3_(MOSI{slash}PCINT3))") (class "Default")
      (node (ref "R24") (pin "2") (pintype "passive"))
      (node (ref "U1") (pin "13") (pinfunction "PB3_(MOSI/PCINT3)_13") (pintype "bidirectional"))
    )
    (net (code "152") (name "Net-(U1-PB5_(SCK{slash}PCINT5))") (class "Default")
      (node (ref "R25") (pin "2") (pintype "passive"))
      (node (ref "U1") (pin "15") (pinfunction "PB5_(SCK/PCINT5)_15") (pintype "bidirectional"))
    )
    (net (code "153") (name "Net-(U1-PB7_(PCINT7))") (class "Default")
      (node (ref "R18") (pin "2") (pintype "passive"))
      (node (ref "U1") (pin "6") (pinfunction "PB7_(PCINT7)_6") (pintype "bidirectional"))
    )
    (net (code "154") (name "unconnected-(K5-Pad2)") (class "Default")
      (node (ref "K5") (pin "2") (pinfunction "2_2") (pintype "passive+no_connect"))
    )
    (net (code "155") (name "unconnected-(K5-Pad7)") (class "Default")
      (node (ref "K5") (pin "7") (pinfunction "7_7") (pintype "passive+no_connect"))
    )
    (net (code "156") (name "unconnected-(K6-Pad2)") (class "Default")
      (node (ref "K6") (pin "2") (pinfunction "2_2") (pintype "passive+no_connect"))
    )
    (net (code "157") (name "unconnected-(K6-Pad7)") (class "Default")
      (node (ref "K6") (pin "7") (pinfunction "7_7") (pintype "passive+no_connect"))
    )
    (net (code "158") (name "unconnected-(K7-Pad2)") (class "Default")
      (node (ref "K7") (pin "2") (pinfunction "2_2") (pintype "passive+no_connect"))
    )
    (net (code "159") (name "unconnected-(K7-Pad7)") (class "Default")
      (node (ref "K7") (pin "7") (pinfunction "7_7") (pintype "passive+no_connect"))
    )
    (net (code "160") (name "unconnected-(K8-Pad2)") (class "Default")
      (node (ref "K8") (pin "2") (pinfunction "2_2") (pintype "passive+no_connect"))
    )
    (net (code "161") (name "unconnected-(K8-Pad7)") (class "Default")
      (node (ref "K8") (pin "7") (pinfunction "7_7") (pintype "passive+no_connect"))
    )
    (net (code "162") (name "unconnected-(K13-Pad2)") (class "Default")
      (node (ref "K13") (pin "2") (pinfunction "2_2") (pintype "passive+no_connect"))
    )
    (net (code "163") (name "unconnected-(K13-Pad7)") (class "Default")
      (node (ref "K13") (pin "7") (pinfunction "7_7") (pintype "passive+no_connect"))
    )
    (net (code "164") (name "unconnected-(K14-Pad2)") (class "Default")
      (node (ref "K14") (pin "2") (pinfunction "2_2") (pintype "passive+no_connect"))
    )
    (net (code "165") (name "unconnected-(K14-Pad7)") (class "Default")
      (node (ref "K14") (pin "7") (pinfunction "7_7") (pintype "passive+no_connect"))
    )
    (net (code "166") (name "unconnected-(K15-Pad2)") (class "Default")
      (node (ref "K15") (pin "2") (pinfunction "2_2") (pintype "passive+no_connect"))
    )
    (net (code "167") (name "unconnected-(K15-Pad7)") (class "Default")
      (node (ref "K15") (pin "7") (pinfunction "7_7") (pintype "passive+no_connect"))
    )
    (net (code "168") (name "unconnected-(K16-Pad2)") (class "Default")
      (node (ref "K16") (pin "2") (pinfunction "2_2") (pintype "passive+no_connect"))
    )
    (net (code "169") (name "unconnected-(K16-Pad7)") (class "Default")
      (node (ref "K16") (pin "7") (pinfunction "7_7") (pintype "passive+no_connect"))
    )
    (net (code "170") (name "unconnected-(LD1-N{slash}C-Pad4)") (class "Default")
      (node (ref "LD1") (pin "4") (pinfunction "N/C_4") (pintype "passive+no_connect"))
    )
    (net (code "171") (name "unconnected-(MCP1-INTA-Pad16)") (class "Default")
      (node (ref "MCP1") (pin "16") (pinfunction "INTA_16") (pintype "passive+no_connect"))
    )
    (net (code "172") (name "unconnected-(MCP1-INTB-Pad15)") (class "Default")
      (node (ref "MCP1") (pin "15") (pinfunction "INTB_15") (pintype "passive+no_connect"))
    )
    (net (code "173") (name "unconnected-(U1-PB0_(PCINT0{slash}CLKO{slash}ICP1)-Pad10)") (class "Default")
      (node (ref "U1") (pin "10") (pinfunction "PB0_(PCINT0/CLKO/ICP1)_10") (pintype "bidirectional"))
    )
    (net (code "174") (name "unconnected-(U1-PB1_(OC1A{slash}PCINT1)-Pad11)") (class "Default")
      (node (ref "U1") (pin "11") (pinfunction "PB1_(OC1A/PCINT1)_11") (pintype "bidirectional"))
    )
    (net (code "175") (name "unconnected-(U1-PB6_(PCINT6{slash}CLKI)-Pad5)") (class "Default")
      (node (ref "U1") (pin "5") (pinfunction "PB6_(PCINT6/CLKI)_5") (pintype "bidirectional"))
    )
    (net (code "176") (name "unconnected-(U1-PC0_(ADC0{slash}PCINT8)-Pad19)") (class "Default")
      (node (ref "U1") (pin "19") (pinfunction "PC0_(ADC0/PCINT8)_19") (pintype "bidirectional"))
    )
    (net (code "177") (name "unconnected-(U1-PC1_(ADC1{slash}PCINT9)-Pad20)") (class "Default")
      (node (ref "U1") (pin "20") (pinfunction "PC1_(ADC1/PCINT9)_20") (pintype "bidirectional"))
    )
    (net (code "178") (name "unconnected-(U1-PC2_(ADC2{slash}PCINT10)-Pad21)") (class "Default")
      (node (ref "U1") (pin "21") (pinfunction "PC2_(ADC2/PCINT10)_21") (pintype "bidirectional"))
    )
    (net (code "179") (name "unconnected-(U1-PC3_(ADC3{slash}PCINT11)-Pad22)") (class "Default")
      (node (ref "U1") (pin "22") (pinfunction "PC3_(ADC3/PCINT11)_22") (pintype "bidirectional"))
    )
    (net (code "180") (name "unconnected-(U1-PC7_(PCINT15)-Pad17)") (class "Default")
      (node (ref "U1") (pin "17") (pinfunction "PC7_(PCINT15)_17") (pintype "bidirectional"))
    )
    (net (code "181") (name "unconnected-(U1-PD0_(PCINT16)-Pad26)") (class "Default")
      (node (ref "U1") (pin "26") (pinfunction "PD0_(PCINT16)_26") (pintype "bidirectional"))
    )
    (net (code "182") (name "unconnected-(U1-PD1_(PCINT17)-Pad27)") (class "Default")
      (node (ref "U1") (pin "27") (pinfunction "PD1_(PCINT17)_27") (pintype "bidirectional"))
    )
    (net (code "183") (name "unconnected-(U1-PD2_(PCINT18{slash}INT0)-Pad28)") (class "Default")
      (node (ref "U1") (pin "28") (pinfunction "PD2_(PCINT18/INT0)_28") (pintype "bidirectional"))
    )
    (net (code "184") (name "unconnected-(U1-PD3_(PCINT19{slash}INT1)-Pad1)") (class "Default")
      (node (ref "U1") (pin "1") (pinfunction "PD3_(PCINT19/INT1)_1") (pintype "bidirectional"))
    )
    (net (code "185") (name "unconnected-(U1-PD4_(PCINT20{slash}T0)-Pad2)") (class "Default")
      (node (ref "U1") (pin "2") (pinfunction "PD4_(PCINT20/T0)_2") (pintype "bidirectional"))
    )
    (net (code "186") (name "unconnected-(U1-PD5_(PCINT21{slash}T1)-Pad7)") (class "Default")
      (node (ref "U1") (pin "7") (pinfunction "PD5_(PCINT21/T1)_7") (pintype "bidirectional"))
    )
    (net (code "187") (name "unconnected-(U1-PD6_(PCINT22{slash}AIN0)-Pad8)") (class "Default")
      (node (ref "U1") (pin "8") (pinfunction "PD6_(PCINT22/AIN0)_8") (pintype "bidirectional"))
    )
    (net (code "188") (name "unconnected-(U1-PD7_(PCINT23{slash}AIN1)-Pad9)") (class "Default")
      (node (ref "U1") (pin "9") (pinfunction "PD7_(PCINT23/AIN1)_9") (pintype "bidirectional"))
    )
  )
)
